# top.net
KiCad netlist of a schematic drawn in Altium Designer
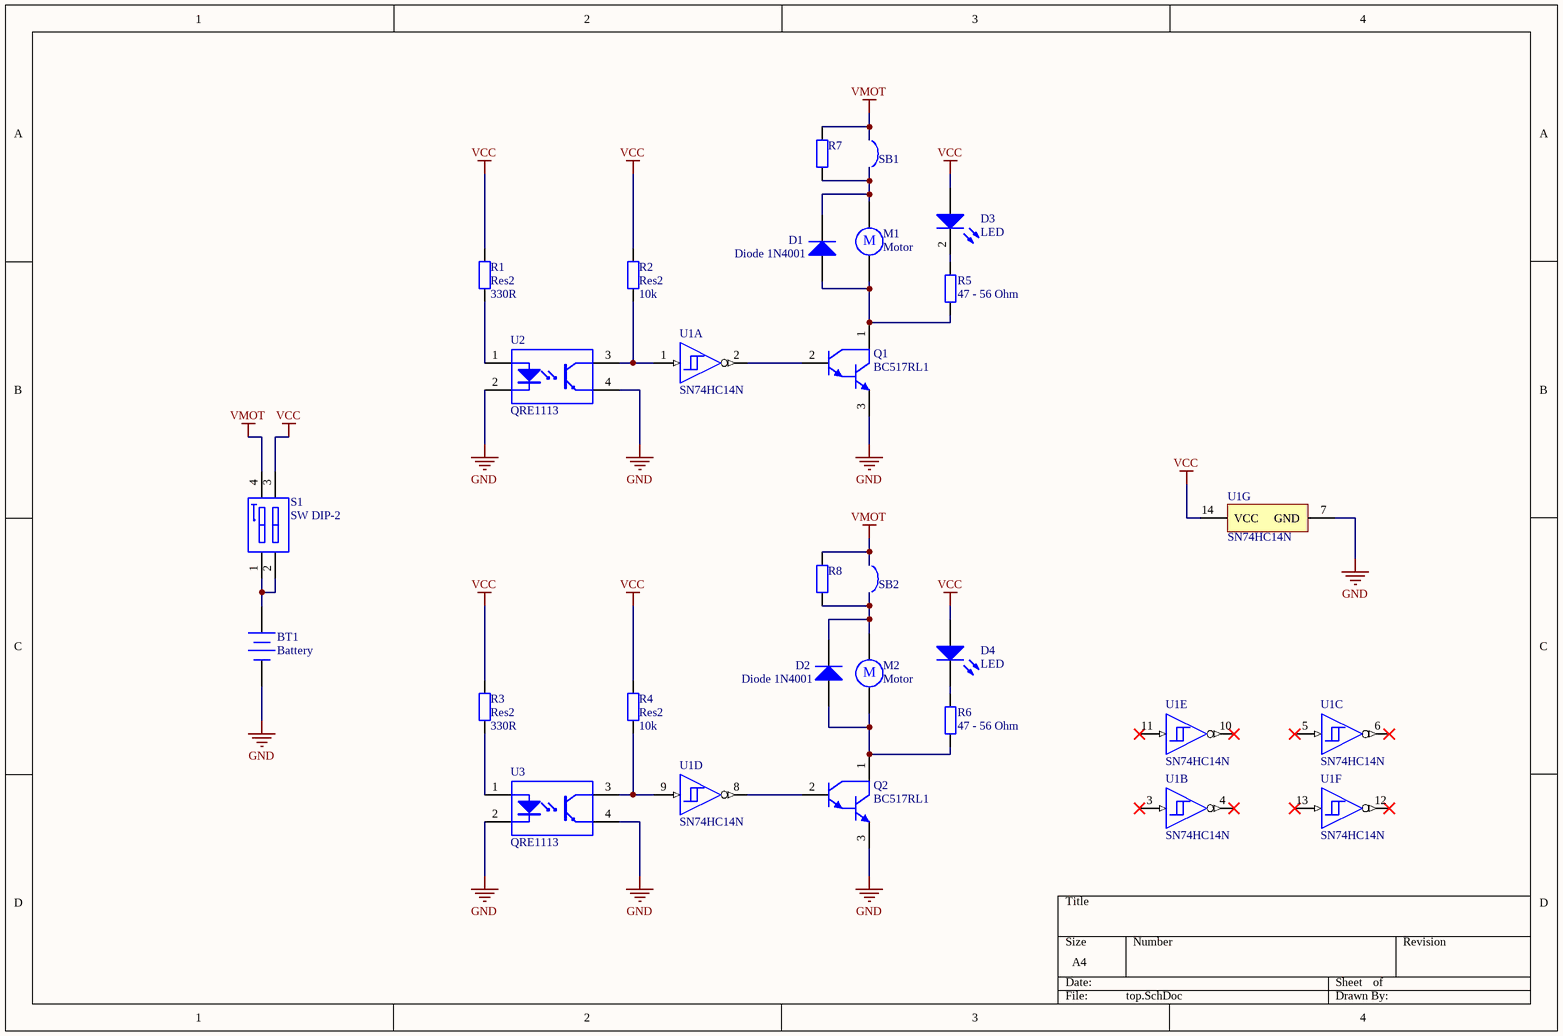
[diagram p0: top.SchDoc]

(export (version "E")
  (design (tool "Eeschema 10.0.6"))
  (components
    (comp (ref "BT1")
      (value "Battery")
      (footprint "BC2AAPC")
      (description "Multicell Battery")
      (fields (field (name "PUBLISHER") "Altium Limited"))
      (libsource (lib "Miscellaneous Devices") (part "Battery"))
    )
    (comp (ref "D1")
      (value "Diode 1N4001")
      (footprint "DO-41")
      (description "1 Amp General Purpose Rectifier")
      (fields (field (name "PUBLISHER") "Altium Limited"))
      (libsource (lib "Miscellaneous Devices") (part "Diode 1N4001"))
    )
    (comp (ref "D2")
      (value "Diode 1N4001")
      (footprint "DO-41")
      (description "1 Amp General Purpose Rectifier")
      (fields (field (name "PUBLISHER") "Altium Limited"))
      (libsource (lib "Miscellaneous Devices") (part "Diode 1N4001"))
    )
    (comp (ref "D3")
      (value "LED")
      (footprint "LED")
      (description "Typical INFRARED GaAs LED")
      (fields (field (name "PUBLISHER") "Altium Limited"))
      (libsource (lib "Miscellaneous Devices") (part "LED0"))
    )
    (comp (ref "D4")
      (value "LED")
      (footprint "LED")
      (description "Typical INFRARED GaAs LED")
      (fields (field (name "PUBLISHER") "Altium Limited"))
      (libsource (lib "") (part "LED0_1"))
    )
    (comp (ref "M1")
      (value "Motor")
      (footprint "Motor Wire Footprint")
      (description "Motor, General Kind")
      (fields (field (name "PUBLISHER") "Altium Limited"))
      (libsource (lib "components") (part "Motor"))
    )
    (comp (ref "M2")
      (value "Motor")
      (footprint "Motor Wire Footprint")
      (description "Motor, General Kind")
      (fields (field (name "PUBLISHER") "Altium Limited"))
      (libsource (lib "components") (part "Motor"))
    )
    (comp (ref "Q1")
      (value "BC517RL1")
      (footprint "ONSC-TO-92-3-29-11_AM_BL")
      (description "Darlington Transistor, NPN Silicon, 3-Pin TO-92, Tape and Reel")
      (fields (field (name "MANUFACTURER") "On Semiconductor"))
      (libsource (lib "Altium Content Vault") (part "ONSC-DT-NPN-C1B2E3-3"))
    )
    (comp (ref "Q2")
      (value "BC517RL1")
      (footprint "ONSC-TO-92-3-29-11_AM_BL")
      (description "Darlington Transistor, NPN Silicon, 3-Pin TO-92, Tape and Reel")
      (fields (field (name "MANUFACTURER") "On Semiconductor"))
      (libsource (lib "Altium Content Vault") (part "ONSC-DT-NPN-C1B2E3-3"))
    )
    (comp (ref "R1")
      (value "Res2")
      (footprint "AXIAL-0.4")
      (description "Resistor")
      (fields (field (name "ALTIUM_VALUE") "330R") (field (name "PUBLISHER") "Altium Limited"))
      (libsource (lib "Miscellaneous Devices") (part "Res2"))
    )
    (comp (ref "R2")
      (value "Res2")
      (footprint "AXIAL-0.4")
      (description "Resistor")
      (fields (field (name "ALTIUM_VALUE") "10k") (field (name "PUBLISHER") "Altium Limited"))
      (libsource (lib "Miscellaneous Devices") (part "Res2"))
    )
    (comp (ref "R3")
      (value "Res2")
      (footprint "AXIAL-0.4")
      (description "Resistor")
      (fields (field (name "ALTIUM_VALUE") "330R") (field (name "PUBLISHER") "Altium Limited"))
      (libsource (lib "Miscellaneous Devices") (part "Res2"))
    )
    (comp (ref "R4")
      (value "Res2")
      (footprint "AXIAL-0.4")
      (description "Resistor")
      (fields (field (name "ALTIUM_VALUE") "10k") (field (name "PUBLISHER") "Altium Limited"))
      (libsource (lib "Miscellaneous Devices") (part "Res2"))
    )
    (comp (ref "R5")
      (value "47 - 56 Ohm")
      (footprint "AXIAL-0.4")
      (description "Resistor")
      (fields (field (name "Comment") "Res2") (field (name "PUBLISHER") "Altium Limited"))
      (libsource (lib "Miscellaneous Devices") (part "Res2"))
    )
    (comp (ref "R6")
      (value "47 - 56 Ohm")
      (footprint "AXIAL-0.4")
      (description "Resistor")
      (fields (field (name "Comment") "Res2") (field (name "PUBLISHER") "Altium Limited"))
      (libsource (lib "Miscellaneous Devices") (part "Res2"))
    )
    (comp (ref "R7")
      (value "Res2")
      (footprint "AXIAL-0.4")
      (description "Resistor")
      (fields (field (name "PUBLISHER") "Altium Limited"))
      (libsource (lib "Miscellaneous Devices") (part "Res2"))
    )
    (comp (ref "R8")
      (value "Res2")
      (footprint "AXIAL-0.4")
      (description "Resistor")
      (fields (field (name "PUBLISHER") "Altium Limited"))
      (libsource (lib "Miscellaneous Devices") (part "Res2"))
    )
    (comp (ref "S1")
      (value "SW DIP-2")
      (footprint "DIP-4")
      (description "DIP Switch, 2 Position, SPST")
      (fields (field (name "PUBLISHER") "Altium Limited"))
      (libsource (lib "Miscellaneous Devices") (part "SW DIP-2"))
    )
    (comp (ref "SB1")
      (value "Solder Bridge")
      (footprint "Solder Bridge")
      (libsource (lib "components") (part "Solder Bridge"))
    )
    (comp (ref "SB2")
      (value "Solder Bridge")
      (footprint "Solder Bridge")
      (libsource (lib "components") (part "Solder Bridge"))
    )
    (comp (ref "U1")
      (value "SN74HC14N")
      (footprint "N0014A")
      (description "Hex Schmitt-Trigger Inverters, N0014A, TUBE")
      (fields
        (field (name "MANUFACTURER") "Texas Instruments")
        (field (name "GENERIC PART NUMBER") "SN74HC14")
      )
      (libsource (lib "Altium Content Vault") (part "TI-CD_SNX4XXXXXX4X_19A-14-SCHMITT"))
    )
    (comp (ref "U2")
      (value "QRE1113")
      (footprint "QRE1113_THD")
      (description "Miniature Reflective Object Sensor, 30 V, -40 to 85 degC, 4-Pin THD, RoHS, Tape and Reel")
      (fields (field (name "MANUFACTURER") "FairchildSemiconductor"))
      (libsource (lib "altium-import") (part "root_0_OPTO-AKCE-4_"))
    )
    (comp (ref "U3")
      (value "QRE1113")
      (footprint "QRE1113_THD")
      (description "Miniature Reflective Object Sensor, 30 V, -40 to 85 degC, 4-Pin THD, RoHS, Tape and Reel")
      (fields (field (name "MANUFACTURER") "FairchildSemiconductor"))
      (libsource (lib "altium-import") (part "root_0_CMP-2000-06919-1_"))
    )
  )
  (nets
    (net (code "1") (name "GND") (class "Default")
      (node (ref "BT1") (pin "2") (pinfunction "-_2") (pintype "passive"))
      (node (ref "Q1") (pin "3") (pinfunction "E_3") (pintype "passive"))
      (node (ref "Q2") (pin "3") (pinfunction "E_3") (pintype "passive"))
      (node (ref "U1") (pin "7") (pinfunction "GND_7") (pintype "power_in"))
      (node (ref "U2") (pin "2") (pinfunction "CATHODE_2") (pintype "passive"))
      (node (ref "U2") (pin "4") (pinfunction "EMITTER_4") (pintype "passive"))
      (node (ref "U3") (pin "2") (pinfunction "CATHODE_2") (pintype "passive"))
      (node (ref "U3") (pin "4") (pinfunction "EMITTER_4") (pintype "passive"))
    )
    (net (code "2") (name "Net-(BT1-+)") (class "Default")
      (node (ref "BT1") (pin "1") (pinfunction "+_1") (pintype "passive"))
      (node (ref "S1") (pin "1") (pinfunction "A1_1") (pintype "passive"))
      (node (ref "S1") (pin "2") (pinfunction "A2_2") (pintype "passive"))
    )
    (net (code "3") (name "Net-(D1-A)") (class "Default")
      (node (ref "D1") (pin "1") (pinfunction "A_1") (pintype "passive"))
      (node (ref "M1") (pin "2") (pinfunction "2_2") (pintype "passive"))
      (node (ref "Q1") (pin "1") (pinfunction "C_1") (pintype "passive"))
      (node (ref "R5") (pin "1") (pinfunction "1_1") (pintype "passive"))
    )
    (net (code "4") (name "Net-(D1-K)") (class "Default")
      (node (ref "D1") (pin "2") (pinfunction "K_2") (pintype "passive"))
      (node (ref "M1") (pin "1") (pinfunction "1_1") (pintype "passive"))
      (node (ref "R7") (pin "1") (pinfunction "1_1") (pintype "passive"))
      (node (ref "SB1") (pin "2") (pinfunction "2_2") (pintype "passive"))
    )
    (net (code "5") (name "Net-(D2-A)") (class "Default")
      (node (ref "D2") (pin "1") (pinfunction "A_1") (pintype "passive"))
      (node (ref "M2") (pin "2") (pinfunction "2_2") (pintype "passive"))
      (node (ref "Q2") (pin "1") (pinfunction "C_1") (pintype "passive"))
      (node (ref "R6") (pin "1") (pinfunction "1_1") (pintype "passive"))
    )
    (net (code "6") (name "Net-(D2-K)") (class "Default")
      (node (ref "D2") (pin "2") (pinfunction "K_2") (pintype "passive"))
      (node (ref "M2") (pin "1") (pinfunction "1_1") (pintype "passive"))
      (node (ref "R8") (pin "1") (pinfunction "1_1") (pintype "passive"))
      (node (ref "SB2") (pin "2") (pinfunction "2_2") (pintype "passive"))
    )
    (net (code "7") (name "Net-(D3-K)") (class "Default")
      (node (ref "D3") (pin "2") (pinfunction "K_2") (pintype "passive"))
      (node (ref "R5") (pin "2") (pinfunction "2_2") (pintype "passive"))
    )
    (net (code "8") (name "Net-(D4-K)") (class "Default")
      (node (ref "D4") (pin "2") (pinfunction "K_2") (pintype "passive"))
      (node (ref "R6") (pin "2") (pinfunction "2_2") (pintype "passive"))
    )
    (net (code "9") (name "Net-(Q1-B)") (class "Default")
      (node (ref "Q1") (pin "2") (pinfunction "B_2") (pintype "passive"))
      (node (ref "U1") (pin "2") (pinfunction "~{1Y}_2") (pintype "output"))
    )
    (net (code "10") (name "Net-(Q2-B)") (class "Default")
      (node (ref "Q2") (pin "2") (pinfunction "B_2") (pintype "passive"))
      (node (ref "U1") (pin "8") (pinfunction "~{4Y}_8") (pintype "output"))
    )
    (net (code "11") (name "Net-(U1A-1A)") (class "Default")
      (node (ref "R2") (pin "1") (pinfunction "1_1") (pintype "passive"))
      (node (ref "U1") (pin "1") (pinfunction "1A_1") (pintype "input"))
      (node (ref "U2") (pin "3") (pinfunction "COLLECTOR_3") (pintype "passive"))
    )
    (net (code "12") (name "Net-(U1D-4A)") (class "Default")
      (node (ref "R4") (pin "1") (pinfunction "1_1") (pintype "passive"))
      (node (ref "U1") (pin "9") (pinfunction "4A_9") (pintype "input"))
      (node (ref "U3") (pin "3") (pinfunction "COLLECTOR_3") (pintype "passive"))
    )
    (net (code "13") (name "Net-(U2-ANODE)") (class "Default")
      (node (ref "R1") (pin "1") (pinfunction "1_1") (pintype "passive"))
      (node (ref "U2") (pin "1") (pinfunction "ANODE_1") (pintype "passive"))
    )
    (net (code "14") (name "Net-(U3-ANODE)") (class "Default")
      (node (ref "R3") (pin "1") (pinfunction "1_1") (pintype "passive"))
      (node (ref "U3") (pin "1") (pinfunction "ANODE_1") (pintype "passive"))
    )
    (net (code "15") (name "VCC") (class "Default")
      (node (ref "D3") (pin "1") (pinfunction "A_1") (pintype "passive"))
      (node (ref "D4") (pin "1") (pinfunction "A_1") (pintype "passive"))
      (node (ref "R1") (pin "2") (pinfunction "2_2") (pintype "passive"))
      (node (ref "R2") (pin "2") (pinfunction "2_2") (pintype "passive"))
      (node (ref "R3") (pin "2") (pinfunction "2_2") (pintype "passive"))
      (node (ref "R4") (pin "2") (pinfunction "2_2") (pintype "passive"))
      (node (ref "S1") (pin "3") (pinfunction "B2_3") (pintype "passive"))
      (node (ref "U1") (pin "14") (pinfunction "VCC_14") (pintype "power_in"))
    )
    (net (code "16") (name "VMOT") (class "Default")
      (node (ref "R7") (pin "2") (pinfunction "2_2") (pintype "passive"))
      (node (ref "R8") (pin "2") (pinfunction "2_2") (pintype "passive"))
      (node (ref "S1") (pin "4") (pinfunction "B1_4") (pintype "passive"))
      (node (ref "SB1") (pin "1") (pinfunction "1_1") (pintype "passive"))
      (node (ref "SB2") (pin "1") (pinfunction "1_1") (pintype "passive"))
    )
    (net (code "17") (name "unconnected-(U1B-2A-Pad3)") (class "Default")
      (node (ref "U1") (pin "3") (pinfunction "2A_3") (pintype "input+no_connect"))
    )
    (net (code "18") (name "unconnected-(U1B-~{2Y}-Pad4)") (class "Default")
      (node (ref "U1") (pin "4") (pinfunction "~{2Y}_4") (pintype "output+no_connect"))
    )
    (net (code "19") (name "unconnected-(U1C-3A-Pad5)") (class "Default")
      (node (ref "U1") (pin "5") (pinfunction "3A_5") (pintype "input+no_connect"))
    )
    (net (code "20") (name "unconnected-(U1C-~{3Y}-Pad6)") (class "Default")
      (node (ref "U1") (pin "6") (pinfunction "~{3Y}_6") (pintype "output+no_connect"))
    )
    (net (code "21") (name "unconnected-(U1E-5A-Pad11)") (class "Default")
      (node (ref "U1") (pin "11") (pinfunction "5A_11") (pintype "input+no_connect"))
    )
    (net (code "22") (name "unconnected-(U1E-~{5Y}-Pad10)") (class "Default")
      (node (ref "U1") (pin "10") (pinfunction "~{5Y}_10") (pintype "output+no_connect"))
    )
    (net (code "23") (name "unconnected-(U1F-6A-Pad13)") (class "Default")
      (node (ref "U1") (pin "13") (pinfunction "6A_13") (pintype "input+no_connect"))
    )
    (net (code "24") (name "unconnected-(U1F-~{6Y}-Pad12)") (class "Default")
      (node (ref "U1") (pin "12") (pinfunction "~{6Y}_12") (pintype "output+no_connect"))
    )
  )
)
